# Power_Distribution.net
KiCad netlist of a schematic drawn in EAGLE
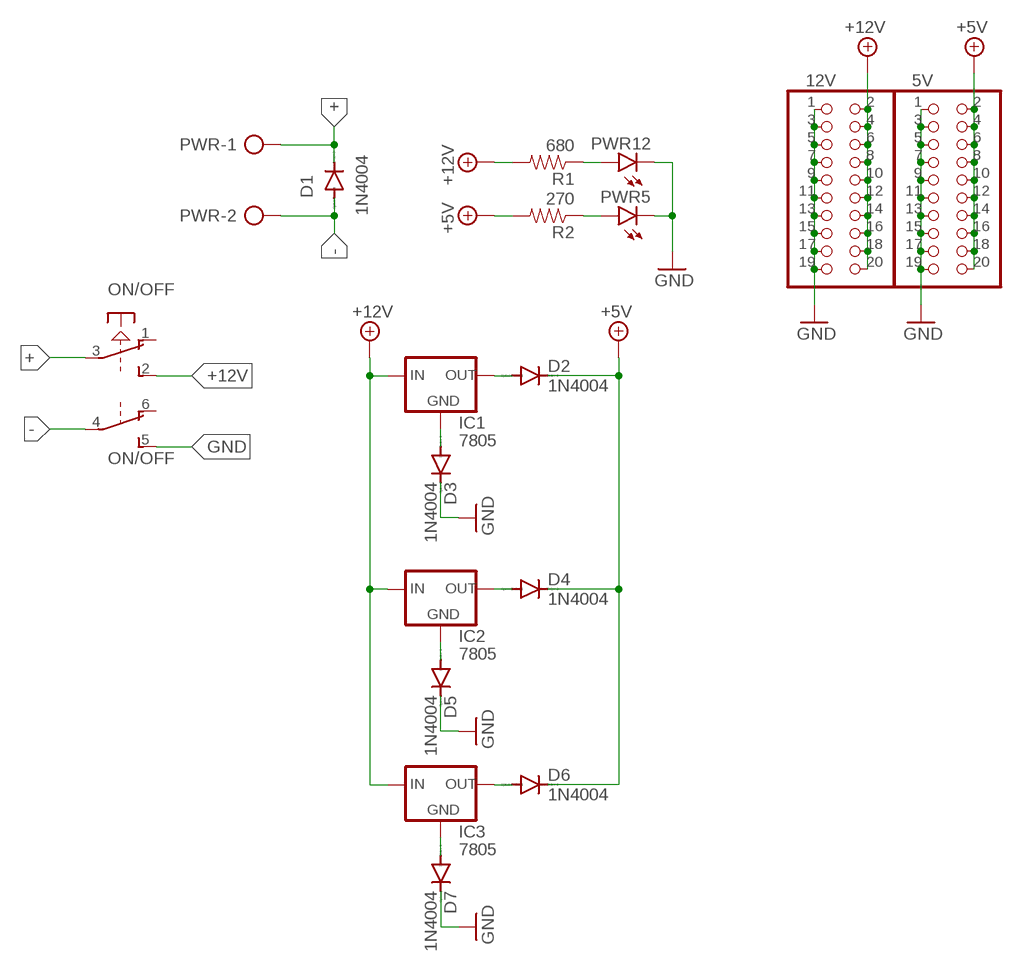
[diagram p0: schematic, sheet 1]

(export (version "E")
  (design (tool "Eeschema 10.0.6"))
  (components
    (comp (ref "5V")
      (value "PINHD-2X10")
      (footprint "eagle-import:2X10")
      (libsource (lib "eagle-import") (part "PINHD-2X10"))
    )
    (comp (ref "12V")
      (value "PINHD-2X10")
      (footprint "eagle-import:2X10")
      (libsource (lib "eagle-import") (part "PINHD-2X10"))
    )
    (comp (ref "D1")
      (value "1N4004")
      (footprint "eagle-import:DO41-10")
      (libsource (lib "eagle-import") (part "1N4004"))
    )
    (comp (ref "D2")
      (value "1N4004")
      (footprint "eagle-import:DO41-10")
      (libsource (lib "eagle-import") (part "1N4004"))
    )
    (comp (ref "D3")
      (value "1N4004")
      (footprint "eagle-import:DO41-10")
      (libsource (lib "eagle-import") (part "1N4004"))
    )
    (comp (ref "D4")
      (value "1N4004")
      (footprint "eagle-import:DO41-10")
      (libsource (lib "eagle-import") (part "1N4004"))
    )
    (comp (ref "D5")
      (value "1N4004")
      (footprint "eagle-import:DO41-10")
      (libsource (lib "eagle-import") (part "1N4004"))
    )
    (comp (ref "D6")
      (value "1N4004")
      (footprint "eagle-import:DO41-10")
      (libsource (lib "eagle-import") (part "1N4004"))
    )
    (comp (ref "D7")
      (value "1N4004")
      (footprint "eagle-import:DO41-10")
      (libsource (lib "eagle-import") (part "1N4004"))
    )
    (comp (ref "IC1")
      (value "7805")
      (footprint "eagle-import:78XXS")
      (libsource (lib "eagle-import") (part "78XXS"))
    )
    (comp (ref "IC2")
      (value "7805")
      (footprint "eagle-import:78XXS")
      (libsource (lib "eagle-import") (part "78XXS"))
    )
    (comp (ref "IC3")
      (value "7805")
      (footprint "eagle-import:78XXS")
      (libsource (lib "eagle-import") (part "78XXS"))
    )
    (comp (ref "ON/OFF")
      (value "PVA2R")
      (footprint "eagle-import:PVA2R")
      (libsource (lib "eagle-import") (part "PVA2R"))
    )
    (comp (ref "PWR")
      (value "AK500/2-H")
      (footprint "eagle-import:AK500_2-H")
      (libsource (lib "eagle-import") (part "AK500/2-H"))
    )
    (comp (ref "PWR5")
      (value "LED3MM")
      (footprint "eagle-import:LED3MM")
      (libsource (lib "eagle-import") (part "LED3MM"))
    )
    (comp (ref "PWR12")
      (value "LED3MM")
      (footprint "eagle-import:LED3MM")
      (libsource (lib "eagle-import") (part "LED3MM"))
    )
    (comp (ref "R1")
      (value "680")
      (footprint "eagle-import:AXIAL-0.3")
      (libsource (lib "eagle-import") (part "RESISTORAXIAL-0.3"))
    )
    (comp (ref "R2")
      (value "270")
      (footprint "eagle-import:AXIAL-0.3")
      (libsource (lib "eagle-import") (part "RESISTORAXIAL-0.3"))
    )
  )
  (nets
    (net (code "1") (name "+") (class "Default")
      (node (ref "D1") (pin "C") (pinfunction "C_C") (pintype "passive"))
      (node (ref "ON/OFF") (pin "3") (pinfunction "P_3") (pintype "passive"))
      (node (ref "PWR") (pin "1") (pinfunction "KL_1") (pintype "passive"))
    )
    (net (code "2") (name "+5V") (class "Default")
      (node (ref "5V") (pin "10") (pinfunction "10_10") (pintype "passive"))
      (node (ref "5V") (pin "12") (pinfunction "12_12") (pintype "passive"))
      (node (ref "5V") (pin "14") (pinfunction "14_14") (pintype "passive"))
      (node (ref "5V") (pin "16") (pinfunction "16_16") (pintype "passive"))
      (node (ref "5V") (pin "18") (pinfunction "18_18") (pintype "passive"))
      (node (ref "5V") (pin "2") (pinfunction "2_2") (pintype "passive"))
      (node (ref "5V") (pin "20") (pinfunction "20_20") (pintype "passive"))
      (node (ref "5V") (pin "4") (pinfunction "4_4") (pintype "passive"))
      (node (ref "5V") (pin "6") (pinfunction "6_6") (pintype "passive"))
      (node (ref "5V") (pin "8") (pinfunction "8_8") (pintype "passive"))
      (node (ref "D2") (pin "C") (pinfunction "C_C") (pintype "passive"))
      (node (ref "D4") (pin "C") (pinfunction "C_C") (pintype "passive"))
      (node (ref "D6") (pin "C") (pinfunction "C_C") (pintype "passive"))
      (node (ref "R2") (pin "P$2") (pinfunction "2_P$2") (pintype "passive"))
    )
    (net (code "3") (name "+12V") (class "Default")
      (node (ref "12V") (pin "10") (pinfunction "10_10") (pintype "passive"))
      (node (ref "12V") (pin "12") (pinfunction "12_12") (pintype "passive"))
      (node (ref "12V") (pin "14") (pinfunction "14_14") (pintype "passive"))
      (node (ref "12V") (pin "16") (pinfunction "16_16") (pintype "passive"))
      (node (ref "12V") (pin "18") (pinfunction "18_18") (pintype "passive"))
      (node (ref "12V") (pin "2") (pinfunction "2_2") (pintype "passive"))
      (node (ref "12V") (pin "20") (pinfunction "20_20") (pintype "passive"))
      (node (ref "12V") (pin "4") (pinfunction "4_4") (pintype "passive"))
      (node (ref "12V") (pin "6") (pinfunction "6_6") (pintype "passive"))
      (node (ref "12V") (pin "8") (pinfunction "8_8") (pintype "passive"))
      (node (ref "IC1") (pin "IN") (pinfunction "IN_IN") (pintype "input"))
      (node (ref "IC2") (pin "IN") (pinfunction "IN_IN") (pintype "input"))
      (node (ref "IC3") (pin "IN") (pinfunction "IN_IN") (pintype "input"))
      (node (ref "ON/OFF") (pin "2") (pinfunction "S_2") (pintype "passive"))
      (node (ref "R1") (pin "P$2") (pinfunction "2_P$2") (pintype "passive"))
    )
    (net (code "4") (name "-") (class "Default")
      (node (ref "D1") (pin "A") (pinfunction "A_A") (pintype "passive"))
      (node (ref "ON/OFF") (pin "4") (pinfunction "P_4") (pintype "passive"))
      (node (ref "PWR") (pin "2") (pinfunction "KL_2") (pintype "passive"))
    )
    (net (code "5") (name "GND") (class "Default")
      (node (ref "12V") (pin "1") (pinfunction "1_1") (pintype "passive"))
      (node (ref "12V") (pin "11") (pinfunction "11_11") (pintype "passive"))
      (node (ref "12V") (pin "13") (pinfunction "13_13") (pintype "passive"))
      (node (ref "12V") (pin "15") (pinfunction "15_15") (pintype "passive"))
      (node (ref "12V") (pin "17") (pinfunction "17_17") (pintype "passive"))
      (node (ref "12V") (pin "19") (pinfunction "19_19") (pintype "passive"))
      (node (ref "12V") (pin "3") (pinfunction "3_3") (pintype "passive"))
      (node (ref "12V") (pin "5") (pinfunction "5_5") (pintype "passive"))
      (node (ref "12V") (pin "7") (pinfunction "7_7") (pintype "passive"))
      (node (ref "12V") (pin "9") (pinfunction "9_9") (pintype "passive"))
      (node (ref "5V") (pin "1") (pinfunction "1_1") (pintype "passive"))
      (node (ref "5V") (pin "11") (pinfunction "11_11") (pintype "passive"))
      (node (ref "5V") (pin "13") (pinfunction "13_13") (pintype "passive"))
      (node (ref "5V") (pin "15") (pinfunction "15_15") (pintype "passive"))
      (node (ref "5V") (pin "17") (pinfunction "17_17") (pintype "passive"))
      (node (ref "5V") (pin "19") (pinfunction "19_19") (pintype "passive"))
      (node (ref "5V") (pin "3") (pinfunction "3_3") (pintype "passive"))
      (node (ref "5V") (pin "5") (pinfunction "5_5") (pintype "passive"))
      (node (ref "5V") (pin "7") (pinfunction "7_7") (pintype "passive"))
      (node (ref "5V") (pin "9") (pinfunction "9_9") (pintype "passive"))
      (node (ref "D3") (pin "C") (pinfunction "C_C") (pintype "passive"))
      (node (ref "D5") (pin "C") (pinfunction "C_C") (pintype "passive"))
      (node (ref "D7") (pin "C") (pinfunction "C_C") (pintype "passive"))
      (node (ref "ON/OFF") (pin "5") (pinfunction "S_5") (pintype "passive"))
      (node (ref "PWR12") (pin "K") (pinfunction "C_K") (pintype "passive"))
      (node (ref "PWR5") (pin "K") (pinfunction "C_K") (pintype "passive"))
    )
    (net (code "6") (name "Net-(D2-PadA)") (class "Default")
      (node (ref "D2") (pin "A") (pinfunction "A_A") (pintype "passive"))
      (node (ref "IC1") (pin "OUT") (pinfunction "OUT_OUT") (pintype "passive"))
    )
    (net (code "7") (name "Net-(D3-PadA)") (class "Default")
      (node (ref "D3") (pin "A") (pinfunction "A_A") (pintype "passive"))
      (node (ref "IC1") (pin "GND") (pinfunction "GND_GND") (pintype "input"))
    )
    (net (code "8") (name "Net-(D4-PadA)") (class "Default")
      (node (ref "D4") (pin "A") (pinfunction "A_A") (pintype "passive"))
      (node (ref "IC2") (pin "OUT") (pinfunction "OUT_OUT") (pintype "passive"))
    )
    (net (code "9") (name "Net-(D5-PadA)") (class "Default")
      (node (ref "D5") (pin "A") (pinfunction "A_A") (pintype "passive"))
      (node (ref "IC2") (pin "GND") (pinfunction "GND_GND") (pintype "input"))
    )
    (net (code "10") (name "Net-(D6-PadA)") (class "Default")
      (node (ref "D6") (pin "A") (pinfunction "A_A") (pintype "passive"))
      (node (ref "IC3") (pin "OUT") (pinfunction "OUT_OUT") (pintype "passive"))
    )
    (net (code "11") (name "Net-(D7-PadA)") (class "Default")
      (node (ref "D7") (pin "A") (pinfunction "A_A") (pintype "passive"))
      (node (ref "IC3") (pin "GND") (pinfunction "GND_GND") (pintype "input"))
    )
    (net (code "12") (name "Net-(R1-1)") (class "Default")
      (node (ref "PWR12") (pin "A") (pinfunction "A_A") (pintype "passive"))
      (node (ref "R1") (pin "P$1") (pinfunction "1_P$1") (pintype "passive"))
    )
    (net (code "13") (name "Net-(R2-1)") (class "Default")
      (node (ref "PWR5") (pin "A") (pinfunction "A_A") (pintype "passive"))
      (node (ref "R2") (pin "P$1") (pinfunction "1_P$1") (pintype "passive"))
    )
    (net (code "14") (name "unconnected-(ON/OFFA-O-Pad1)") (class "Default")
      (node (ref "ON/OFF") (pin "1") (pinfunction "O_1") (pintype "passive"))
    )
    (net (code "15") (name "unconnected-(ON/OFFB-O-Pad6)") (class "Default")
      (node (ref "ON/OFF") (pin "6") (pinfunction "O_6") (pintype "passive"))
    )
  )
)
